# Downstream.net
KiCad netlist of a schematic drawn in Altium Designer
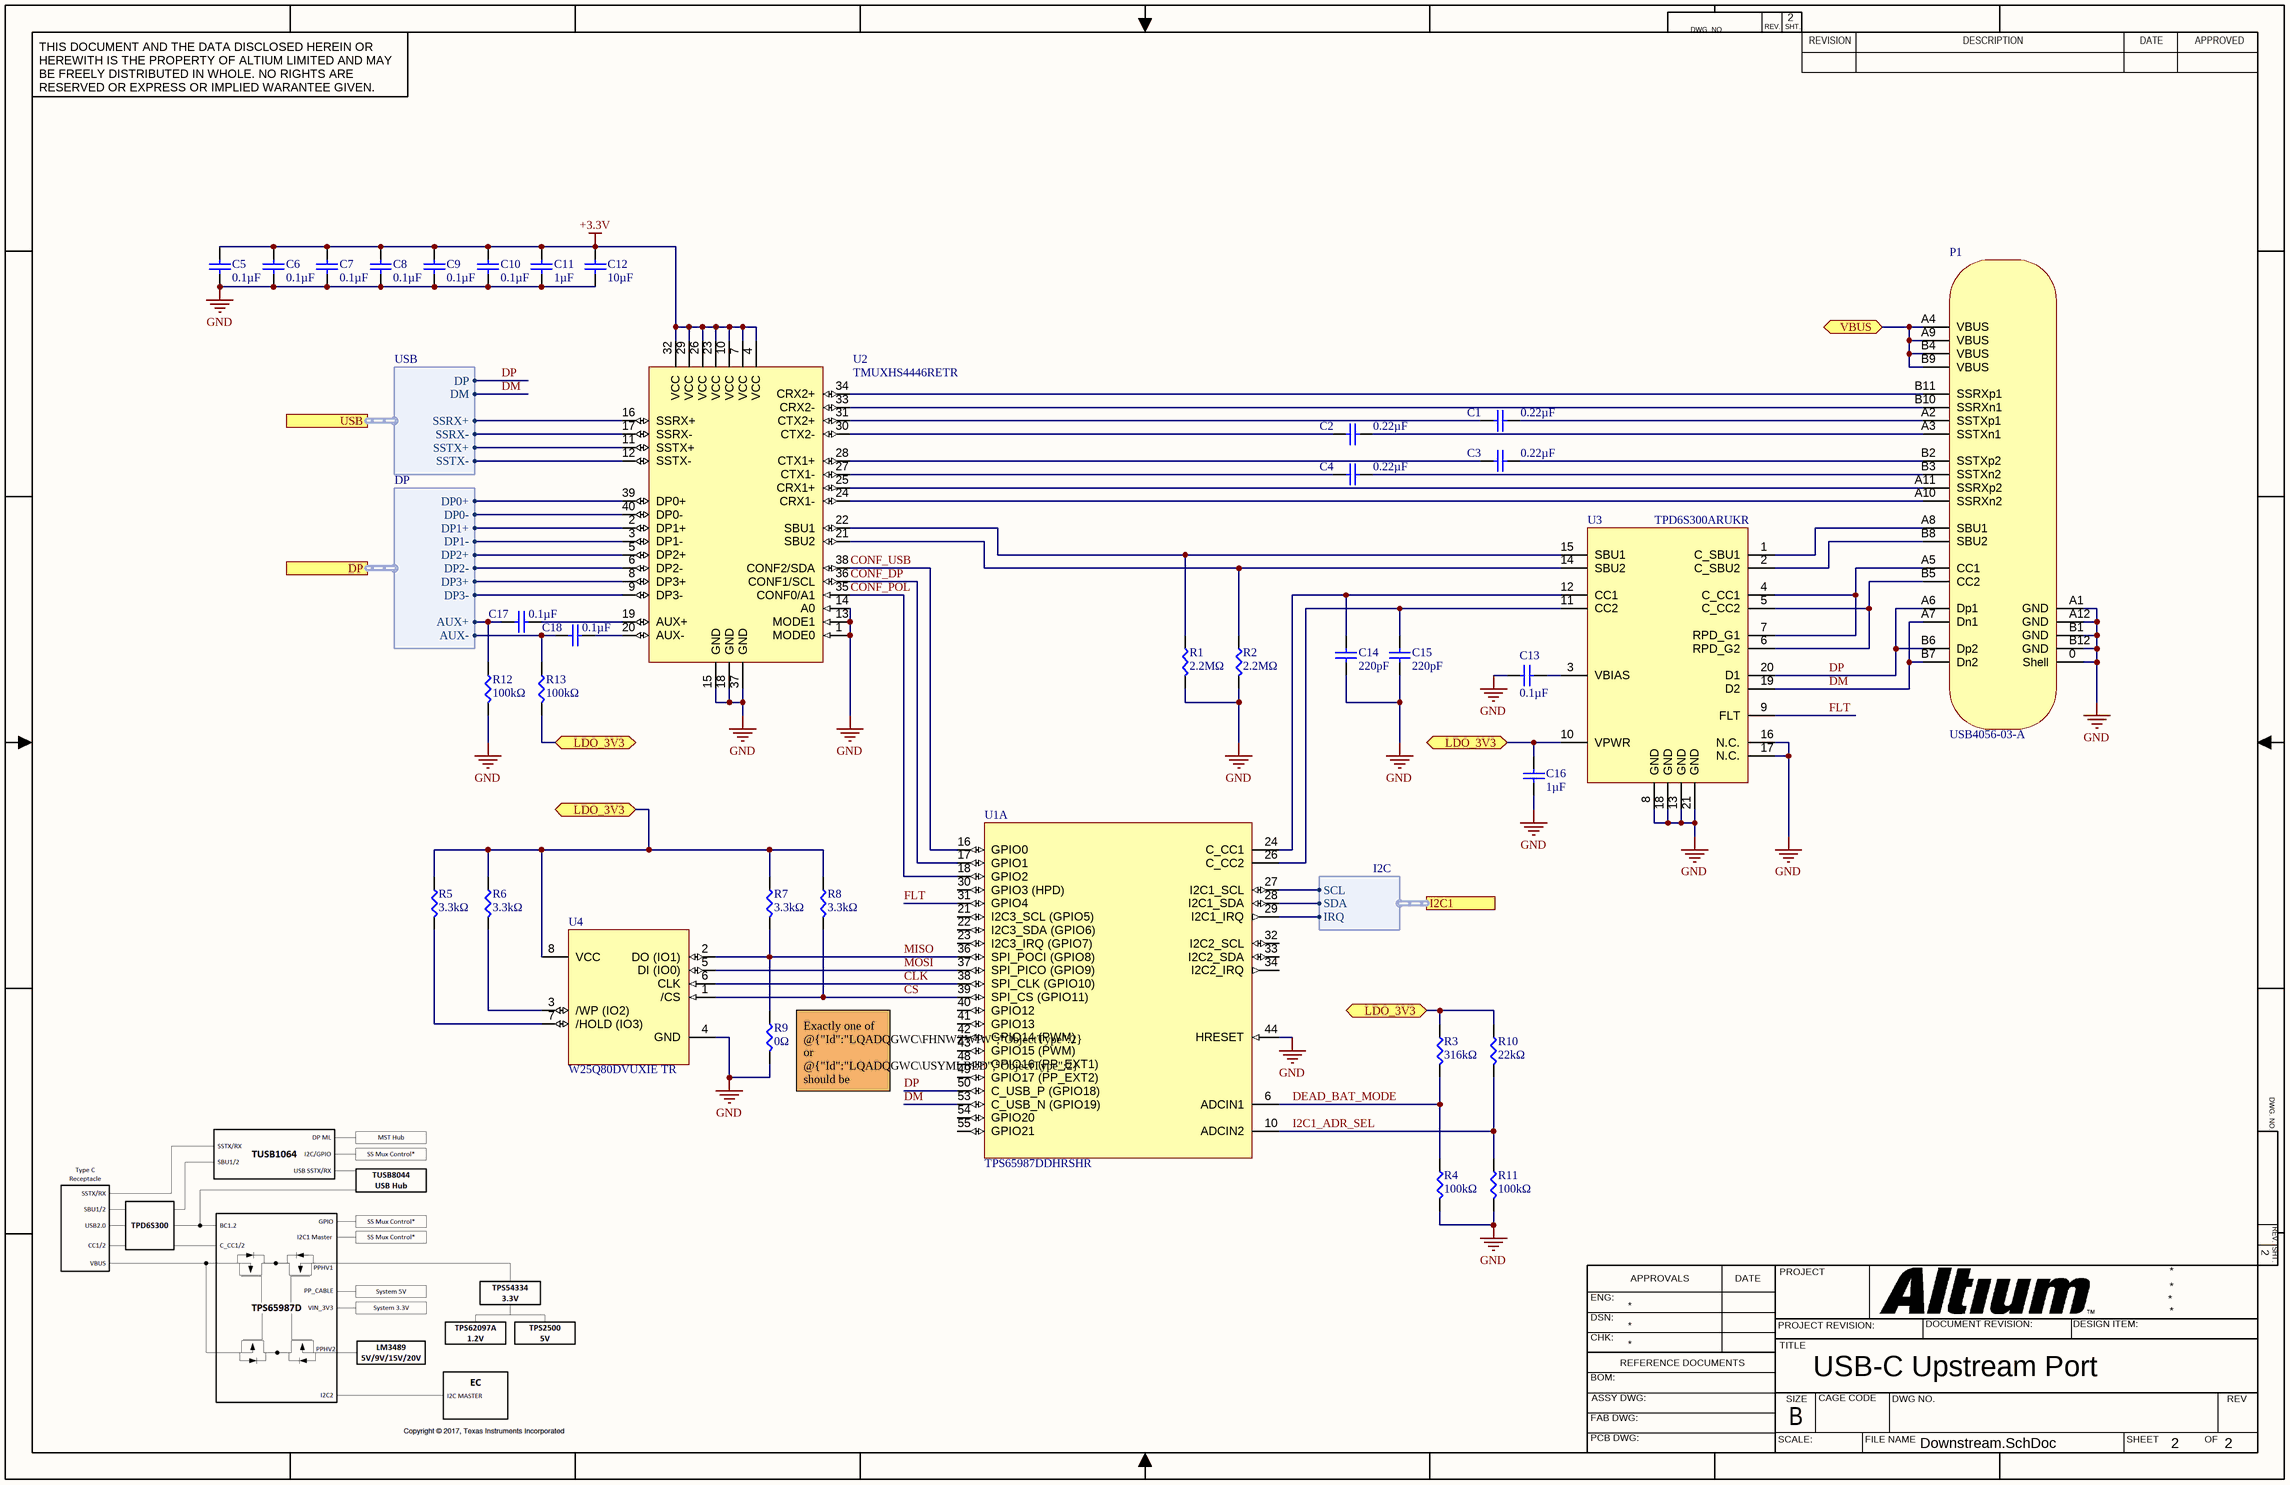
[diagram p0: Downstream.SchDoc]

(export (version "E")
  (design (tool "Eeschema 10.0.6"))
  (components
    (comp (ref "C1")
      (value "0.22µF")
      (footprint "CAP0402")
      (description "0.22 µF ±10% 50V Ceramic Capacitor X5R 0402 (1005 Metric)")
      (fields (field (name "VOLTAGE") "50V") (field (name "Comment") "UMK105BJ224KV-F"))
      (libsource (lib "Schlib1") (part "UMK105BJ224KV-F"))
    )
    (comp (ref "C2")
      (value "0.22µF")
      (footprint "CAP0402")
      (description "0.22 µF ±10% 50V Ceramic Capacitor X5R 0402 (1005 Metric)")
      (fields (field (name "VOLTAGE") "50V") (field (name "Comment") "UMK105BJ224KV-F"))
      (libsource (lib "Schlib1") (part "UMK105BJ224KV-F"))
    )
    (comp (ref "C3")
      (value "0.22µF")
      (footprint "CAP0402")
      (description "0.22 µF ±10% 50V Ceramic Capacitor X5R 0402 (1005 Metric)")
      (fields (field (name "VOLTAGE") "50V") (field (name "Comment") "UMK105BJ224KV-F"))
      (libsource (lib "Schlib1") (part "UMK105BJ224KV-F"))
    )
    (comp (ref "C4")
      (value "0.22µF")
      (footprint "CAP0402")
      (description "0.22 µF ±10% 50V Ceramic Capacitor X5R 0402 (1005 Metric)")
      (fields (field (name "VOLTAGE") "50V") (field (name "Comment") "UMK105BJ224KV-F"))
      (libsource (lib "Schlib1") (part "UMK105BJ224KV-F"))
    )
    (comp (ref "C5")
      (value "0.1µF")
      (footprint "CAP0402")
      (description "0.1 µF ±10% 50V Ceramic Capacitor X5R 0402 (1005 Metric)")
      (fields (field (name "VOLTAGE") "50V") (field (name "Comment") "CC0402KRX5R9BB104"))
      (libsource (lib "Schlib1") (part "CC0402KRX5R9BB104"))
    )
    (comp (ref "C6")
      (value "0.1µF")
      (footprint "CAP0402")
      (description "0.1 µF ±10% 50V Ceramic Capacitor X5R 0402 (1005 Metric)")
      (fields (field (name "VOLTAGE") "50V") (field (name "Comment") "CC0402KRX5R9BB104"))
      (libsource (lib "Schlib1") (part "CC0402KRX5R9BB104"))
    )
    (comp (ref "C7")
      (value "0.1µF")
      (footprint "CAP0402")
      (description "0.1 µF ±10% 50V Ceramic Capacitor X5R 0402 (1005 Metric)")
      (fields (field (name "VOLTAGE") "50V") (field (name "Comment") "CC0402KRX5R9BB104"))
      (libsource (lib "Schlib1") (part "CC0402KRX5R9BB104"))
    )
    (comp (ref "C8")
      (value "0.1µF")
      (footprint "CAP0402")
      (description "0.1 µF ±10% 50V Ceramic Capacitor X5R 0402 (1005 Metric)")
      (fields (field (name "VOLTAGE") "50V") (field (name "Comment") "CC0402KRX5R9BB104"))
      (libsource (lib "Schlib1") (part "CC0402KRX5R9BB104"))
    )
    (comp (ref "C9")
      (value "0.1µF")
      (footprint "CAP0402")
      (description "0.1 µF ±10% 50V Ceramic Capacitor X5R 0402 (1005 Metric)")
      (fields (field (name "VOLTAGE") "50V") (field (name "Comment") "CC0402KRX5R9BB104"))
      (libsource (lib "Schlib1") (part "CC0402KRX5R9BB104"))
    )
    (comp (ref "C10")
      (value "0.1µF")
      (footprint "CAP0402")
      (description "0.1 µF ±10% 50V Ceramic Capacitor X5R 0402 (1005 Metric)")
      (fields (field (name "VOLTAGE") "50V") (field (name "Comment") "CC0402KRX5R9BB104"))
      (libsource (lib "Schlib1") (part "CC0402KRX5R9BB104"))
    )
    (comp (ref "C11")
      (value "1µF")
      (footprint "CAP0402")
      (description "1 µF ±10% 16V Ceramic Capacitor X5R 0402 (1005 Metric)")
      (fields (field (name "VOLTAGE") "16V") (field (name "Comment") "CL05A105KO5NNNC"))
      (libsource (lib "Schlib1") (part "CL05A105KO5NNNC"))
    )
    (comp (ref "C12")
      (value "10µF")
      (footprint "CAP0402")
      (description "10 µF ±20% 6.3V Ceramic Capacitor X5R 0402 (1005 Metric)")
      (fields (field (name "VOLTAGE") "6.3V") (field (name "Comment") "CL05A106MQ5NUNC"))
      (libsource (lib "Schlib1") (part "CL05A106MQ5NUNC"))
    )
    (comp (ref "C13")
      (value "0.1µF")
      (footprint "CAP0402")
      (description "0.1 µF ±10% 50V Ceramic Capacitor X5R 0402 (1005 Metric)")
      (fields (field (name "VOLTAGE") "50V") (field (name "Comment") "CC0402KRX5R9BB104"))
      (libsource (lib "Schlib1") (part "CC0402KRX5R9BB104"))
    )
    (comp (ref "C14")
      (value "220pF")
      (footprint "CAP0402")
      (description "220 pF ±5% 50V Ceramic Capacitor C0G, NP0 0402 (1005 Metric)")
      (fields (field (name "VOLTAGE") "50V") (field (name "Comment") "GRM1555C1H221JA01D"))
      (libsource (lib "Schlib1") (part "GRM1555C1H221JA01D"))
    )
    (comp (ref "C15")
      (value "220pF")
      (footprint "CAP0402")
      (description "220 pF ±5% 50V Ceramic Capacitor C0G, NP0 0402 (1005 Metric)")
      (fields (field (name "VOLTAGE") "50V") (field (name "Comment") "GRM1555C1H221JA01D"))
      (libsource (lib "Schlib1") (part "GRM1555C1H221JA01D"))
    )
    (comp (ref "C16")
      (value "1µF")
      (footprint "CAP0402")
      (description "1 µF ±10% 16V Ceramic Capacitor X5R 0402 (1005 Metric)")
      (fields (field (name "VOLTAGE") "16V") (field (name "Comment") "CL05A105KO5NNNC"))
      (libsource (lib "Schlib1") (part "CL05A105KO5NNNC"))
    )
    (comp (ref "C17")
      (value "0.1µF")
      (footprint "CAP0402")
      (description "0.1 µF ±10% 50V Ceramic Capacitor X5R 0402 (1005 Metric)")
      (fields (field (name "VOLTAGE") "50V") (field (name "Comment") "CC0402KRX5R9BB104"))
      (libsource (lib "Schlib1") (part "CC0402KRX5R9BB104"))
    )
    (comp (ref "C18")
      (value "0.1µF")
      (footprint "CAP0402")
      (description "0.1 µF ±10% 50V Ceramic Capacitor X5R 0402 (1005 Metric)")
      (fields (field (name "VOLTAGE") "50V") (field (name "Comment") "CC0402KRX5R9BB104"))
      (libsource (lib "Schlib1") (part "CC0402KRX5R9BB104"))
    )
    (comp (ref "P1")
      (value "USB4056-03-A")
      (footprint "USB4056-03-A")
      (fields (field (name "MANUFACTURER") "GCT") (field (name "VOLTAGE") "48VDC"))
      (libsource (lib "Schlib1") (part "USB4056-03-A"))
    )
    (comp (ref "R1")
      (value "2.2MΩ")
      (footprint "RES0402")
      (description "2.2 MOhms ±1% 0.063W, 1/16W Chip Resistor 0402 (1005 Metric) Moisture Resistant Thick Film")
      (fields (field (name "Comment") "RC0402FR-072M2L"))
      (libsource (lib "Schlib1") (part "RC0402FR-072M2L"))
    )
    (comp (ref "R2")
      (value "2.2MΩ")
      (footprint "RES0402")
      (description "2.2 MOhms ±1% 0.063W, 1/16W Chip Resistor 0402 (1005 Metric) Moisture Resistant Thick Film")
      (fields (field (name "Comment") "RC0402FR-072M2L"))
      (libsource (lib "Schlib1") (part "RC0402FR-072M2L"))
    )
    (comp (ref "R3")
      (value "316kΩ")
      (footprint "RES0402")
      (description "316 kOhms ±1% 0.1W, 1/10W Chip Resistor 0402 (1005 Metric) Automotive AEC-Q200 Thick Film")
      (fields (field (name "Comment") "CRCW0402316KFKED"))
      (libsource (lib "Schlib1") (part "CRCW0402316KFKED"))
    )
    (comp (ref "R4")
      (value "100kΩ")
      (footprint "RES0402")
      (description "100 kOhms ±1% 0.1W, 1/10W Chip Resistor 0402 (1005 Metric) Automotive AEC-Q200 Thick Film")
      (fields (field (name "Comment") "ERJ-2RKF1003X"))
      (libsource (lib "Schlib1") (part "ERJ-2RKF1003X"))
    )
    (comp (ref "R5")
      (value "3.3kΩ")
      (footprint "RES0402")
      (description "3.3 kOhms ±0.1% 0.063W, 1/16W Chip Resistor 0402 (1005 Metric) Automotive AEC-Q200 Thin Film")
      (fields (field (name "Comment") "ERA-2AEB332X"))
      (libsource (lib "Schlib1") (part "ERA-2AEB332X"))
    )
    (comp (ref "R6")
      (value "3.3kΩ")
      (footprint "RES0402")
      (description "3.3 kOhms ±0.1% 0.063W, 1/16W Chip Resistor 0402 (1005 Metric) Automotive AEC-Q200 Thin Film")
      (fields (field (name "Comment") "ERA-2AEB332X"))
      (libsource (lib "Schlib1") (part "ERA-2AEB332X"))
    )
    (comp (ref "R7")
      (value "3.3kΩ")
      (footprint "RES0402")
      (description "3.3 kOhms ±0.1% 0.063W, 1/16W Chip Resistor 0402 (1005 Metric) Automotive AEC-Q200 Thin Film")
      (fields (field (name "Comment") "ERA-2AEB332X"))
      (libsource (lib "Schlib1") (part "ERA-2AEB332X"))
    )
    (comp (ref "R8")
      (value "3.3kΩ")
      (footprint "RES0402")
      (description "3.3 kOhms ±0.1% 0.063W, 1/16W Chip Resistor 0402 (1005 Metric) Automotive AEC-Q200 Thin Film")
      (fields (field (name "Comment") "ERA-2AEB332X"))
      (libsource (lib "Schlib1") (part "ERA-2AEB332X"))
    )
    (comp (ref "R9")
      (value "0Ω")
      (footprint "RES0402")
      (description "0 Ohms Jumper Chip Resistor 0402 (1005 Metric) Moisture Resistant Thick Film")
      (fields (field (name "Comment") "RC0402JR-070RL"))
      (libsource (lib "Schlib1") (part "RC0402JR-070RL"))
    )
    (comp (ref "R10")
      (value "22kΩ")
      (footprint "RES0402")
      (description "22 kOhms ±1% 0.1W, 1/10W Chip Resistor 0402 (1005 Metric) Automotive AEC-Q200 Thick Film")
      (fields (field (name "Comment") "ERJ-2RKF2202X"))
      (libsource (lib "Schlib1") (part "ERJ-2RKF2202X"))
    )
    (comp (ref "R11")
      (value "100kΩ")
      (footprint "RES0402")
      (description "100 kOhms ±1% 0.1W, 1/10W Chip Resistor 0402 (1005 Metric) Automotive AEC-Q200 Thick Film")
      (fields (field (name "Comment") "ERJ-2RKF1003X"))
      (libsource (lib "Schlib1") (part "ERJ-2RKF1003X"))
    )
    (comp (ref "R12")
      (value "100kΩ")
      (footprint "RES0402")
      (description "100 kOhms ±1% 0.1W, 1/10W Chip Resistor 0402 (1005 Metric) Automotive AEC-Q200 Thick Film")
      (fields (field (name "Comment") "ERJ-2RKF1003X"))
      (libsource (lib "Schlib1") (part "ERJ-2RKF1003X"))
    )
    (comp (ref "R13")
      (value "100kΩ")
      (footprint "RES0402")
      (description "100 kOhms ±1% 0.1W, 1/10W Chip Resistor 0402 (1005 Metric) Automotive AEC-Q200 Thick Film")
      (fields (field (name "Comment") "ERJ-2RKF1003X"))
      (libsource (lib "Schlib1") (part "ERJ-2RKF1003X"))
    )
    (comp (ref "U1")
      (value "TPS65987DDHRSHR")
      (footprint "56-VQFN (7x7)")
      (description "USB, Type-C Controller PMIC 56-VQFN (7x7)")
      (fields (field (name "MANUFACTURER") "Texas Instruments"))
      (libsource (lib "Schlib1") (part "TPS65987DDHRSHR"))
    )
    (comp (ref "U2")
      (value "TMUXHS4446RETR")
      (description "4 Circuit IC Switch 4:4 7Ohm (Typ) 40-WQFN (6x3)")
      (fields (field (name "MANUFACTURER") "Texas Instruments"))
      (libsource (lib "Schlib1") (part "TMUXHS4446RETR"))
    )
    (comp (ref "U3")
      (value "TPD6S300ARUKR")
      (description "Overvoltage/Surge Protection IC 8V Internal Switch 20-WQFN (3x3)")
      (fields (field (name "MANUFACTURER") "Texas Instruments"))
      (libsource (lib "Schlib1") (part "TPD6S300ARUKR"))
    )
    (comp (ref "U4")
      (value "W25Q80DVUXIE TR")
      (description "FLASH - NOR Memory IC 8Mbit SPI - Quad I/O 104 MHz 8-USON (2x3)")
      (fields (field (name "MANUFACTURER") "Winbond Electronics"))
      (libsource (lib "Schlib1") (part "W25Q80DVUXIE TR"))
    )
  )
  (nets
    (net (code "3") (name "+3.3V") (class "Default")
      (node (ref "C10") (pin "2") (pinfunction "2_2") (pintype "passive"))
      (node (ref "C11") (pin "2") (pinfunction "2_2") (pintype "passive"))
      (node (ref "C12") (pin "2") (pinfunction "2_2") (pintype "passive"))
      (node (ref "C5") (pin "2") (pinfunction "2_2") (pintype "passive"))
      (node (ref "C6") (pin "2") (pinfunction "2_2") (pintype "passive"))
      (node (ref "C7") (pin "2") (pinfunction "2_2") (pintype "passive"))
      (node (ref "C8") (pin "2") (pinfunction "2_2") (pintype "passive"))
      (node (ref "C9") (pin "2") (pinfunction "2_2") (pintype "passive"))
      (node (ref "U2") (pin "10") (pinfunction "VCC_10") (pintype "passive"))
      (node (ref "U2") (pin "23") (pinfunction "VCC_23") (pintype "passive"))
      (node (ref "U2") (pin "26") (pinfunction "VCC_26") (pintype "passive"))
      (node (ref "U2") (pin "29") (pinfunction "VCC_29") (pintype "passive"))
      (node (ref "U2") (pin "32") (pinfunction "VCC_32") (pintype "passive"))
      (node (ref "U2") (pin "4") (pinfunction "VCC_4") (pintype "passive"))
      (node (ref "U2") (pin "7") (pinfunction "VCC_7") (pintype "passive"))
    )
    (net (code "4") (name "/AUX+") (class "Default")
      (node (ref "C17") (pin "1") (pinfunction "1_1") (pintype "passive"))
      (node (ref "R12") (pin "2") (pinfunction "2_2") (pintype "passive"))
    )
    (net (code "5") (name "/AUX-") (class "Default")
      (node (ref "C18") (pin "1") (pinfunction "1_1") (pintype "passive"))
      (node (ref "R13") (pin "2") (pinfunction "2_2") (pintype "passive"))
    )
    (net (code "6") (name "/CLK") (class "Default")
      (node (ref "U1") (pin "38") (pinfunction "SPI_CLK_(GPIO10)_38") (pintype "bidirectional"))
      (node (ref "U4") (pin "6") (pinfunction "CLK_6") (pintype "input"))
    )
    (net (code "7") (name "/CONF_DP") (class "Default")
      (node (ref "U1") (pin "17") (pinfunction "GPIO1_17") (pintype "bidirectional"))
      (node (ref "U2") (pin "36") (pinfunction "CONF1/SCL_36") (pintype "bidirectional"))
    )
    (net (code "8") (name "/CONF_POL") (class "Default")
      (node (ref "U1") (pin "18") (pinfunction "GPIO2_18") (pintype "bidirectional"))
      (node (ref "U2") (pin "35") (pinfunction "CONF0/A1_35") (pintype "input"))
    )
    (net (code "9") (name "/CONF_USB") (class "Default")
      (node (ref "U1") (pin "16") (pinfunction "GPIO0_16") (pintype "bidirectional"))
      (node (ref "U2") (pin "38") (pinfunction "CONF2/SDA_38") (pintype "bidirectional"))
    )
    (net (code "10") (name "/CS") (class "Default")
      (node (ref "R8") (pin "1") (pinfunction "1_1") (pintype "passive"))
      (node (ref "U1") (pin "39") (pinfunction "SPI_CS_(GPIO11)_39") (pintype "bidirectional"))
      (node (ref "U4") (pin "1") (pinfunction "/CS_1") (pintype "input"))
    )
    (net (code "11") (name "/DEAD_BAT_MODE") (class "Default")
      (node (ref "R3") (pin "1") (pinfunction "1_1") (pintype "passive"))
      (node (ref "R4") (pin "2") (pinfunction "2_2") (pintype "passive"))
      (node (ref "U1") (pin "6") (pinfunction "ADCIN1_6") (pintype "passive"))
    )
    (net (code "12") (name "/DM") (class "Default")
      (node (ref "P1") (pin "A7") (pinfunction "Dn1_A7") (pintype "passive"))
      (node (ref "P1") (pin "B7") (pinfunction "Dn2_B7") (pintype "passive"))
      (node (ref "U1") (pin "53") (pinfunction "C_USB_N_(GPIO19)_53") (pintype "bidirectional"))
      (node (ref "U3") (pin "19") (pinfunction "D2_19") (pintype "passive"))
    )
    (net (code "13") (name "/DP") (class "Default")
      (node (ref "P1") (pin "A6") (pinfunction "Dp1_A6") (pintype "passive"))
      (node (ref "P1") (pin "B6") (pinfunction "Dp2_B6") (pintype "passive"))
      (node (ref "U1") (pin "50") (pinfunction "C_USB_P_(GPIO18)_50") (pintype "bidirectional"))
      (node (ref "U3") (pin "20") (pinfunction "D1_20") (pintype "passive"))
    )
    (net (code "14") (name "/DP0+") (class "Default")
      (node (ref "U2") (pin "39") (pinfunction "DP0+_39") (pintype "bidirectional"))
    )
    (net (code "15") (name "/DP0-") (class "Default")
      (node (ref "U2") (pin "40") (pinfunction "DP0-_40") (pintype "bidirectional"))
    )
    (net (code "16") (name "/DP1+") (class "Default")
      (node (ref "U2") (pin "2") (pinfunction "DP1+_2") (pintype "bidirectional"))
    )
    (net (code "17") (name "/DP1-") (class "Default")
      (node (ref "U2") (pin "3") (pinfunction "DP1-_3") (pintype "bidirectional"))
    )
    (net (code "18") (name "/DP2+") (class "Default")
      (node (ref "U2") (pin "5") (pinfunction "DP2+_5") (pintype "bidirectional"))
    )
    (net (code "19") (name "/DP2-") (class "Default")
      (node (ref "U2") (pin "6") (pinfunction "DP2-_6") (pintype "bidirectional"))
    )
    (net (code "20") (name "/DP3+") (class "Default")
      (node (ref "U2") (pin "8") (pinfunction "DP3+_8") (pintype "bidirectional"))
    )
    (net (code "21") (name "/DP3-") (class "Default")
      (node (ref "U2") (pin "9") (pinfunction "DP3-_9") (pintype "bidirectional"))
    )
    (net (code "22") (name "/FLT") (class "Default")
      (node (ref "U1") (pin "31") (pinfunction "GPIO4_31") (pintype "bidirectional"))
      (node (ref "U3") (pin "9") (pinfunction "FLT_9") (pintype "passive"))
    )
    (net (code "23") (name "/I2C1_ADR_SEL") (class "Default")
      (node (ref "R10") (pin "1") (pinfunction "1_1") (pintype "passive"))
      (node (ref "R11") (pin "2") (pinfunction "2_2") (pintype "passive"))
      (node (ref "U1") (pin "10") (pinfunction "ADCIN2_10") (pintype "passive"))
    )
    (net (code "24") (name "/IRQ") (class "Default")
      (node (ref "U1") (pin "29") (pinfunction "I2C1_IRQ_29") (pintype "output"))
    )
    (net (code "25") (name "/LDO_3V3") (class "Default")
      (node (ref "C16") (pin "2") (pinfunction "2_2") (pintype "passive"))
      (node (ref "R10") (pin "2") (pinfunction "2_2") (pintype "passive"))
      (node (ref "R13") (pin "1") (pinfunction "1_1") (pintype "passive"))
      (node (ref "R3") (pin "2") (pinfunction "2_2") (pintype "passive"))
      (node (ref "R5") (pin "2") (pinfunction "2_2") (pintype "passive"))
      (node (ref "R6") (pin "2") (pinfunction "2_2") (pintype "passive"))
      (node (ref "R7") (pin "2") (pinfunction "2_2") (pintype "passive"))
      (node (ref "R8") (pin "2") (pinfunction "2_2") (pintype "passive"))
      (node (ref "U3") (pin "10") (pinfunction "VPWR_10") (pintype "passive"))
      (node (ref "U4") (pin "8") (pinfunction "VCC_8") (pintype "passive"))
    )
    (net (code "26") (name "/MISO") (class "Default")
      (node (ref "R7") (pin "1") (pinfunction "1_1") (pintype "passive"))
      (node (ref "R9") (pin "2") (pinfunction "2_2") (pintype "passive"))
      (node (ref "U1") (pin "36") (pinfunction "SPI_POCI_(GPIO8)_36") (pintype "bidirectional"))
      (node (ref "U4") (pin "2") (pinfunction "DO_(IO1)_2") (pintype "bidirectional"))
    )
    (net (code "27") (name "/MOSI") (class "Default")
      (node (ref "U1") (pin "37") (pinfunction "SPI_PICO_(GPIO9)_37") (pintype "bidirectional"))
      (node (ref "U4") (pin "5") (pinfunction "DI_(IO0)_5") (pintype "bidirectional"))
    )
    (net (code "28") (name "/SCL") (class "Default")
      (node (ref "U1") (pin "27") (pinfunction "I2C1_SCL_27") (pintype "bidirectional"))
    )
    (net (code "29") (name "/SDA") (class "Default")
      (node (ref "U1") (pin "28") (pinfunction "I2C1_SDA_28") (pintype "bidirectional"))
    )
    (net (code "30") (name "/SSRX+") (class "Default")
      (node (ref "U2") (pin "16") (pinfunction "SSRX+_16") (pintype "bidirectional"))
    )
    (net (code "31") (name "/SSRX-") (class "Default")
      (node (ref "U2") (pin "17") (pinfunction "SSRX-_17") (pintype "bidirectional"))
    )
    (net (code "32") (name "/SSTX+") (class "Default")
      (node (ref "U2") (pin "11") (pinfunction "SSTX+_11") (pintype "bidirectional"))
    )
    (net (code "33") (name "/SSTX-") (class "Default")
      (node (ref "U2") (pin "12") (pinfunction "SSTX-_12") (pintype "bidirectional"))
    )
    (net (code "34") (name "/VBUS") (class "Default")
      (node (ref "P1") (pin "A4") (pinfunction "VBUS_A4") (pintype "passive"))
      (node (ref "P1") (pin "A9") (pinfunction "VBUS_A9") (pintype "passive"))
      (node (ref "P1") (pin "B4") (pinfunction "VBUS_B4") (pintype "passive"))
      (node (ref "P1") (pin "B9") (pinfunction "VBUS_B9") (pintype "passive"))
    )
    (net (code "38") (name "GND") (class "Default")
      (node (ref "C10") (pin "1") (pinfunction "1_1") (pintype "passive"))
      (node (ref "C11") (pin "1") (pinfunction "1_1") (pintype "passive"))
      (node (ref "C12") (pin "1") (pinfunction "1_1") (pintype "passive"))
      (node (ref "C13") (pin "1") (pinfunction "1_1") (pintype "passive"))
      (node (ref "C14") (pin "1") (pinfunction "1_1") (pintype "passive"))
      (node (ref "C15") (pin "1") (pinfunction "1_1") (pintype "passive"))
      (node (ref "C16") (pin "1") (pinfunction "1_1") (pintype "passive"))
      (node (ref "C5") (pin "1") (pinfunction "1_1") (pintype "passive"))
      (node (ref "C6") (pin "1") (pinfunction "1_1") (pintype "passive"))
      (node (ref "C7") (pin "1") (pinfunction "1_1") (pintype "passive"))
      (node (ref "C8") (pin "1") (pinfunction "1_1") (pintype "passive"))
      (node (ref "C9") (pin "1") (pinfunction "1_1") (pintype "passive"))
      (node (ref "P1") (pin "0") (pinfunction "Shell_0") (pintype "passive"))
      (node (ref "P1") (pin "A1") (pinfunction "GND_A1") (pintype "passive"))
      (node (ref "P1") (pin "A12") (pinfunction "GND_A12") (pintype "passive"))
      (node (ref "P1") (pin "B1") (pinfunction "GND_B1") (pintype "passive"))
      (node (ref "P1") (pin "B12") (pinfunction "GND_B12") (pintype "passive"))
      (node (ref "R1") (pin "1") (pinfunction "1_1") (pintype "passive"))
      (node (ref "R11") (pin "1") (pinfunction "1_1") (pintype "passive"))
      (node (ref "R12") (pin "1") (pinfunction "1_1") (pintype "passive"))
      (node (ref "R2") (pin "1") (pinfunction "1_1") (pintype "passive"))
      (node (ref "R4") (pin "1") (pinfunction "1_1") (pintype "passive"))
      (node (ref "R9") (pin "1") (pinfunction "1_1") (pintype "passive"))
      (node (ref "U1") (pin "44") (pinfunction "HRESET_44") (pintype "input"))
      (node (ref "U2") (pin "1") (pinfunction "MODE0_1") (pintype "input"))
      (node (ref "U2") (pin "13") (pinfunction "MODE1_13") (pintype "input"))
      (node (ref "U2") (pin "14") (pinfunction "A0_14") (pintype "input"))
      (node (ref "U2") (pin "15") (pinfunction "GND_15") (pintype "passive"))
      (node (ref "U2") (pin "18") (pinfunction "GND_18") (pintype "passive"))
      (node (ref "U2") (pin "37") (pinfunction "GND_37") (pintype "passive"))
      (node (ref "U3") (pin "13") (pinfunction "GND_13") (pintype "passive"))
      (node (ref "U3") (pin "16") (pinfunction "N.C._16") (pintype "passive"))
      (node (ref "U3") (pin "17") (pinfunction "N.C._17") (pintype "passive"))
      (node (ref "U3") (pin "18") (pinfunction "GND_18") (pintype "passive"))
      (node (ref "U3") (pin "21") (pinfunction "GND_21") (pintype "passive"))
      (node (ref "U3") (pin "8") (pinfunction "GND_8") (pintype "passive"))
      (node (ref "U4") (pin "4") (pinfunction "GND_4") (pintype "passive"))
    )
    (net (code "39") (name "Net-(P1-CC1)") (class "Default")
      (node (ref "P1") (pin "A5") (pinfunction "CC1_A5") (pintype "passive"))
      (node (ref "U3") (pin "4") (pinfunction "C_CC1_4") (pintype "passive"))
      (node (ref "U3") (pin "7") (pinfunction "RPD_G1_7") (pintype "passive"))
    )
    (net (code "40") (name "Net-(P1-CC2)") (class "Default")
      (node (ref "P1") (pin "B5") (pinfunction "CC2_B5") (pintype "passive"))
      (node (ref "U3") (pin "5") (pinfunction "C_CC2_5") (pintype "passive"))
      (node (ref "U3") (pin "6") (pinfunction "RPD_G2_6") (pintype "passive"))
    )
    (net (code "41") (name "Net-(P1-SBU1)") (class "Default")
      (node (ref "P1") (pin "A8") (pinfunction "SBU1_A8") (pintype "passive"))
      (node (ref "U3") (pin "1") (pinfunction "C_SBU1_1") (pintype "passive"))
    )
    (net (code "42") (name "Net-(P1-SBU2)") (class "Default")
      (node (ref "P1") (pin "B8") (pinfunction "SBU2_B8") (pintype "passive"))
      (node (ref "U3") (pin "2") (pinfunction "C_SBU2_2") (pintype "passive"))
    )
    (net (code "43") (name "Net-(P1-SSRXn1)") (class "Default")
      (node (ref "P1") (pin "B10") (pinfunction "SSRXn1_B10") (pintype "passive"))
      (node (ref "U2") (pin "33") (pinfunction "CRX2-_33") (pintype "bidirectional"))
    )
    (net (code "44") (name "Net-(P1-SSRXn2)") (class "Default")
      (node (ref "P1") (pin "A10") (pinfunction "SSRXn2_A10") (pintype "passive"))
      (node (ref "U2") (pin "24") (pinfunction "CRX1-_24") (pintype "bidirectional"))
    )
    (net (code "45") (name "Net-(P1-SSRXp1)") (class "Default")
      (node (ref "P1") (pin "B11") (pinfunction "SSRXp1_B11") (pintype "passive"))
      (node (ref "U2") (pin "34") (pinfunction "CRX2+_34") (pintype "bidirectional"))
    )
    (net (code "46") (name "Net-(P1-SSRXp2)") (class "Default")
      (node (ref "P1") (pin "A11") (pinfunction "SSRXp2_A11") (pintype "passive"))
      (node (ref "U2") (pin "25") (pinfunction "CRX1+_25") (pintype "bidirectional"))
    )
    (net (code "47") (name "Net-(P1-SSTXn1)") (class "Default")
      (node (ref "C2") (pin "2") (pinfunction "2_2") (pintype "passive"))
      (node (ref "P1") (pin "A3") (pinfunction "SSTXn1_A3") (pintype "passive"))
    )
    (net (code "48") (name "Net-(P1-SSTXn2)") (class "Default")
      (node (ref "C4") (pin "2") (pinfunction "2_2") (pintype "passive"))
      (node (ref "P1") (pin "B3") (pinfunction "SSTXn2_B3") (pintype "passive"))
    )
    (net (code "49") (name "Net-(P1-SSTXp1)") (class "Default")
      (node (ref "C1") (pin "2") (pinfunction "2_2") (pintype "passive"))
      (node (ref "P1") (pin "A2") (pinfunction "SSTXp1_A2") (pintype "passive"))
    )
    (net (code "50") (name "Net-(P1-SSTXp2)") (class "Default")
      (node (ref "C3") (pin "2") (pinfunction "2_2") (pintype "passive"))
      (node (ref "P1") (pin "B2") (pinfunction "SSTXp2_B2") (pintype "passive"))
    )
    (net (code "51") (name "Net-(U1A-C_CC1)") (class "Default")
      (node (ref "C14") (pin "2") (pinfunction "2_2") (pintype "passive"))
      (node (ref "U1") (pin "24") (pinfunction "C_CC1_24") (pintype "passive"))
      (node (ref "U3") (pin "12") (pinfunction "CC1_12") (pintype "passive"))
    )
    (net (code "52") (name "Net-(U1A-C_CC2)") (class "Default")
      (node (ref "C15") (pin "2") (pinfunction "2_2") (pintype "passive"))
      (node (ref "U1") (pin "26") (pinfunction "C_CC2_26") (pintype "passive"))
      (node (ref "U3") (pin "11") (pinfunction "CC2_11") (pintype "passive"))
    )
    (net (code "53") (name "Net-(U2-AUX+)") (class "Default")
      (node (ref "C17") (pin "2") (pinfunction "2_2") (pintype "passive"))
      (node (ref "U2") (pin "19") (pinfunction "AUX+_19") (pintype "bidirectional"))
    )
    (net (code "54") (name "Net-(U2-AUX-)") (class "Default")
      (node (ref "C18") (pin "2") (pinfunction "2_2") (pintype "passive"))
      (node (ref "U2") (pin "20") (pinfunction "AUX-_20") (pintype "bidirectional"))
    )
    (net (code "55") (name "Net-(U2-CTX1+)") (class "Default")
      (node (ref "C3") (pin "1") (pinfunction "1_1") (pintype "passive"))
      (node (ref "U2") (pin "28") (pinfunction "CTX1+_28") (pintype "bidirectional"))
    )
    (net (code "56") (name "Net-(U2-CTX1-)") (class "Default")
      (node (ref "C4") (pin "1") (pinfunction "1_1") (pintype "passive"))
      (node (ref "U2") (pin "27") (pinfunction "CTX1-_27") (pintype "bidirectional"))
    )
    (net (code "57") (name "Net-(U2-CTX2+)") (class "Default")
      (node (ref "C1") (pin "1") (pinfunction "1_1") (pintype "passive"))
      (node (ref "U2") (pin "31") (pinfunction "CTX2+_31") (pintype "bidirectional"))
    )
    (net (code "58") (name "Net-(U2-CTX2-)") (class "Default")
      (node (ref "C2") (pin "1") (pinfunction "1_1") (pintype "passive"))
      (node (ref "U2") (pin "30") (pinfunction "CTX2-_30") (pintype "bidirectional"))
    )
    (net (code "59") (name "Net-(U2-SBU1)") (class "Default")
      (node (ref "R1") (pin "2") (pinfunction "2_2") (pintype "passive"))
      (node (ref "U2") (pin "22") (pinfunction "SBU1_22") (pintype "bidirectional"))
      (node (ref "U3") (pin "15") (pinfunction "SBU1_15") (pintype "passive"))
    )
    (net (code "60") (name "Net-(U2-SBU2)") (class "Default")
      (node (ref "R2") (pin "2") (pinfunction "2_2") (pintype "passive"))
      (node (ref "U2") (pin "21") (pinfunction "SBU2_21") (pintype "bidirectional"))
      (node (ref "U3") (pin "14") (pinfunction "SBU2_14") (pintype "passive"))
    )
    (net (code "61") (name "Net-(U3-VBIAS)") (class "Default")
      (node (ref "C13") (pin "2") (pinfunction "2_2") (pintype "passive"))
      (node (ref "U3") (pin "3") (pinfunction "VBIAS_3") (pintype "passive"))
    )
    (net (code "62") (name "Net-(U4-{slash}HOLD_(IO3))") (class "Default")
      (node (ref "R5") (pin "1") (pinfunction "1_1") (pintype "passive"))
      (node (ref "U4") (pin "7") (pinfunction "/HOLD_(IO3)_7") (pintype "bidirectional"))
    )
    (net (code "63") (name "Net-(U4-{slash}WP_(IO2))") (class "Default")
      (node (ref "R6") (pin "1") (pinfunction "1_1") (pintype "passive"))
      (node (ref "U4") (pin "3") (pinfunction "/WP_(IO2)_3") (pintype "bidirectional"))
    )
    (net (code "64") (name "unconnected-(U1A-GPIO3_(HPD)-Pad30)") (class "Default")
      (node (ref "U1") (pin "30") (pinfunction "GPIO3_(HPD)_30") (pintype "bidirectional"))
    )
    (net (code "65") (name "unconnected-(U1A-GPIO12-Pad40)") (class "Default")
      (node (ref "U1") (pin "40") (pinfunction "GPIO12_40") (pintype "bidirectional"))
    )
    (net (code "66") (name "unconnected-(U1A-GPIO13-Pad41)") (class "Default")
      (node (ref "U1") (pin "41") (pinfunction "GPIO13_41") (pintype "bidirectional"))
    )
    (net (code "67") (name "unconnected-(U1A-GPIO14_(PWM)-Pad42)") (class "Default")
      (node (ref "U1") (pin "42") (pinfunction "GPIO14_(PWM)_42") (pintype "bidirectional"))
    )
    (net (code "68") (name "unconnected-(U1A-GPIO15_(PWM)-Pad43)") (class "Default")
      (node (ref "U1") (pin "43") (pinfunction "GPIO15_(PWM)_43") (pintype "bidirectional"))
    )
    (net (code "69") (name "unconnected-(U1A-GPIO16_(PP_EXT1)-Pad48)") (class "Default")
      (node (ref "U1") (pin "48") (pinfunction "GPIO16_(PP_EXT1)_48") (pintype "bidirectional"))
    )
    (net (code "70") (name "unconnected-(U1A-GPIO17_(PP_EXT2)-Pad49)") (class "Default")
      (node (ref "U1") (pin "49") (pinfunction "GPIO17_(PP_EXT2)_49") (pintype "bidirectional"))
    )
    (net (code "71") (name "unconnected-(U1A-GPIO20-Pad54)") (class "Default")
      (node (ref "U1") (pin "54") (pinfunction "GPIO20_54") (pintype "bidirectional"))
    )
    (net (code "72") (name "unconnected-(U1A-GPIO21-Pad55)") (class "Default")
      (node (ref "U1") (pin "55") (pinfunction "GPIO21_55") (pintype "bidirectional"))
    )
    (net (code "73") (name "unconnected-(U1A-I2C2_IRQ-Pad34)") (class "Default")
      (node (ref "U1") (pin "34") (pinfunction "I2C2_IRQ_34") (pintype "output"))
    )
    (net (code "74") (name "unconnected-(U1A-I2C2_SCL-Pad32)") (class "Default")
      (node (ref "U1") (pin "32") (pinfunction "I2C2_SCL_32") (pintype "bidirectional"))
    )
    (net (code "75") (name "unconnected-(U1A-I2C2_SDA-Pad33)") (class "Default")
      (node (ref "U1") (pin "33") (pinfunction "I2C2_SDA_33") (pintype "bidirectional"))
    )
    (net (code "76") (name "unconnected-(U1A-I2C3_IRQ_(GPIO7)-Pad23)") (class "Default")
      (node (ref "U1") (pin "23") (pinfunction "I2C3_IRQ_(GPIO7)_23") (pintype "bidirectional"))
    )
    (net (code "77") (name "unconnected-(U1A-I2C3_SCL_(GPIO5)-Pad21)") (class "Default")
      (node (ref "U1") (pin "21") (pinfunction "I2C3_SCL_(GPIO5)_21") (pintype "bidirectional"))
    )
    (net (code "78") (name "unconnected-(U1A-I2C3_SDA_(GPIO6)-Pad22)") (class "Default")
      (node (ref "U1") (pin "22") (pinfunction "I2C3_SDA_(GPIO6)_22") (pintype "bidirectional"))
    )
  )
)
